# power_suply_unit.net
KiCad netlist of a schematic drawn in EAGLE
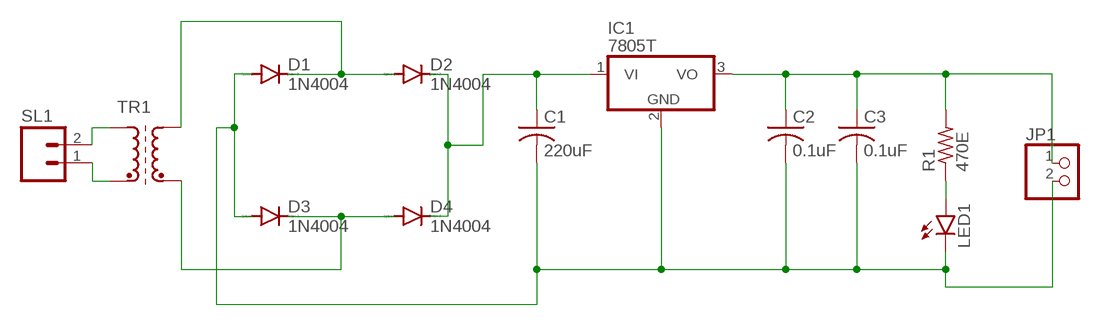
[diagram p0: schematic, sheet 1]

(export (version "E")
  (design (tool "Eeschema 10.0.6"))
  (components
    (comp (ref "C1")
      (value "220uF")
      (footprint "eagle-import:C025-024X044")
      (libsource (lib "eagle-import") (part "C-US025-024X044"))
    )
    (comp (ref "C2")
      (value "0.1uF")
      (footprint "eagle-import:C025-024X044")
      (libsource (lib "eagle-import") (part "C-US025-024X044"))
    )
    (comp (ref "C3")
      (value "0.1uF")
      (footprint "eagle-import:C025-024X044")
      (libsource (lib "eagle-import") (part "C-US025-024X044"))
    )
    (comp (ref "D1")
      (value "1N4004")
      (footprint "eagle-import:DO41-10")
      (libsource (lib "eagle-import") (part "1N4004"))
    )
    (comp (ref "D2")
      (value "1N4004")
      (footprint "eagle-import:DO41-10")
      (libsource (lib "eagle-import") (part "1N4004"))
    )
    (comp (ref "D3")
      (value "1N4004")
      (footprint "eagle-import:DO41-10")
      (libsource (lib "eagle-import") (part "1N4004"))
    )
    (comp (ref "D4")
      (value "1N4004")
      (footprint "eagle-import:DO41-10")
      (libsource (lib "eagle-import") (part "1N4004"))
    )
    (comp (ref "IC1")
      (value "7805T")
      (footprint "eagle-import:TO220H")
      (libsource (lib "eagle-import") (part "78T05"))
    )
    (comp (ref "JP1")
      (value "PINHD-1X2")
      (footprint "eagle-import:1X02")
      (libsource (lib "eagle-import") (part "PINHD-1X2"))
    )
    (comp (ref "LED1")
      (value "LED3MM")
      (footprint "eagle-import:LED3MM")
      (libsource (lib "eagle-import") (part "LED3MM"))
    )
    (comp (ref "R1")
      (value "470E")
      (footprint "eagle-import:0204_7")
      (libsource (lib "eagle-import") (part "R-US_0204/7"))
    )
    (comp (ref "SL1")
      (value "M02")
      (footprint "eagle-import:02P")
      (libsource (lib "eagle-import") (part "M02"))
    )
    (comp (ref "TR1")
      (value "SM-T4")
      (footprint "eagle-import:SM-T4")
      (libsource (lib "eagle-import") (part "SM-T4"))
    )
  )
  (nets
    (net (code "1") (name "Net-(IC1-GND)") (class "Default")
      (node (ref "C1") (pin "2") (pinfunction "2_2") (pintype "passive"))
      (node (ref "C2") (pin "2") (pinfunction "2_2") (pintype "passive"))
      (node (ref "C3") (pin "2") (pinfunction "2_2") (pintype "passive"))
      (node (ref "D1") (pin "A") (pinfunction "A_A") (pintype "passive"))
      (node (ref "D3") (pin "A") (pinfunction "A_A") (pintype "passive"))
      (node (ref "IC1") (pin "2") (pinfunction "GND_2") (pintype "passive"))
      (node (ref "JP1") (pin "2") (pinfunction "2_2") (pintype "passive"))
      (node (ref "LED1") (pin "K") (pinfunction "C_K") (pintype "passive"))
    )
    (net (code "2") (name "Net-(IC1-VI)") (class "Default")
      (node (ref "C1") (pin "1") (pinfunction "1_1") (pintype "passive"))
      (node (ref "D2") (pin "C") (pinfunction "C_C") (pintype "passive"))
      (node (ref "D4") (pin "C") (pinfunction "C_C") (pintype "passive"))
      (node (ref "IC1") (pin "1") (pinfunction "VI_1") (pintype "input"))
    )
    (net (code "3") (name "Net-(IC1-VO)") (class "Default")
      (node (ref "C2") (pin "1") (pinfunction "1_1") (pintype "passive"))
      (node (ref "C3") (pin "1") (pinfunction "1_1") (pintype "passive"))
      (node (ref "IC1") (pin "3") (pinfunction "VO_3") (pintype "passive"))
      (node (ref "JP1") (pin "1") (pinfunction "1_1") (pintype "passive"))
      (node (ref "R1") (pin "2") (pinfunction "2_2") (pintype "passive"))
    )
    (net (code "4") (name "Net-(LED1-PadA)") (class "Default")
      (node (ref "LED1") (pin "A") (pinfunction "A_A") (pintype "passive"))
      (node (ref "R1") (pin "1") (pinfunction "1_1") (pintype "passive"))
    )
    (net (code "5") (name "Net-(TR1-A1)") (class "Default")
      (node (ref "SL1") (pin "2") (pinfunction "2_2") (pintype "passive"))
      (node (ref "TR1") (pin "1") (pinfunction "A1_1") (pintype "passive"))
    )
    (net (code "6") (name "Net-(TR1-A2)") (class "Default")
      (node (ref "D1") (pin "C") (pinfunction "C_C") (pintype "passive"))
      (node (ref "D2") (pin "A") (pinfunction "A_A") (pintype "passive"))
      (node (ref "TR1") (pin "5") (pinfunction "A2_5") (pintype "passive"))
    )
    (net (code "7") (name "Net-(TR1-E1)") (class "Default")
      (node (ref "SL1") (pin "1") (pinfunction "1_1") (pintype "passive"))
      (node (ref "TR1") (pin "2") (pinfunction "E1_2") (pintype "passive"))
    )
    (net (code "8") (name "Net-(TR1-E2)") (class "Default")
      (node (ref "D3") (pin "C") (pinfunction "C_C") (pintype "passive"))
      (node (ref "D4") (pin "A") (pinfunction "A_A") (pintype "passive"))
      (node (ref "TR1") (pin "4") (pinfunction "E2_4") (pintype "passive"))
    )
  )
)
